# Schematic_v2_0.net
KiCad netlist of a schematic drawn in EAGLE
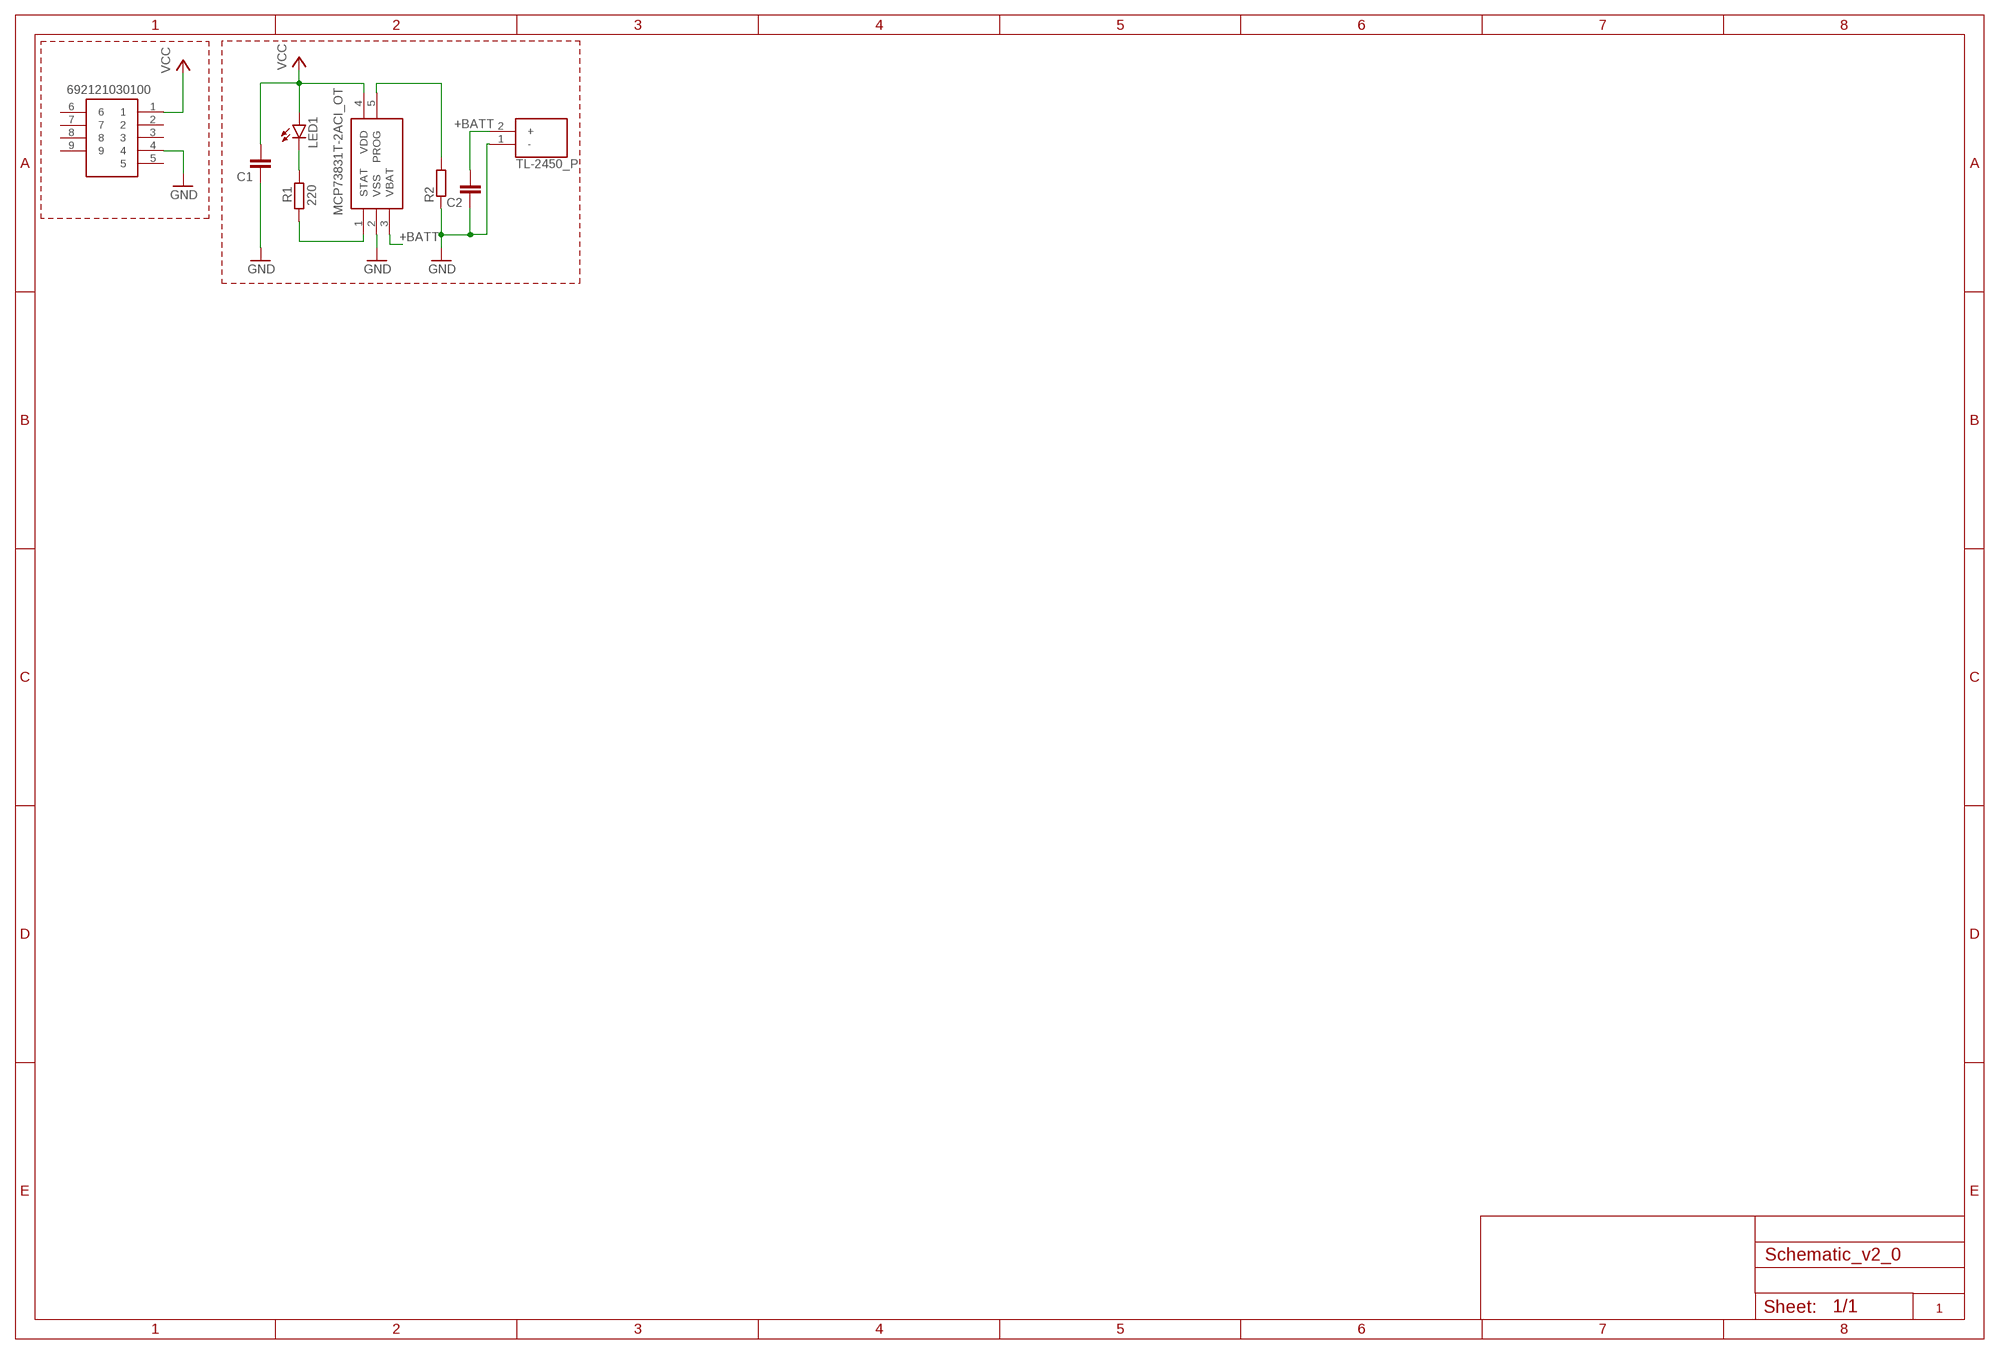
[diagram p0: schematic, sheet 1]

(export (version "E")
  (design (tool "Eeschema 10.0.6"))
  (components
    (comp (ref "BT1")
      (value "TL-2450_P")
      (footprint "eagle-import:TL2450P")
      (fields (field (name "ARROW_PART_NUMBER") "TL-2450/P"))
      (libsource (lib "eagle-import") (part "TL-2450_P"))
    )
    (comp (ref "C1")
      (value "C-EUC0805")
      (footprint "eagle-import:C0805")
      (libsource (lib "eagle-import") (part "C-EUC0805"))
    )
    (comp (ref "C2")
      (value "C-EUC0805")
      (footprint "eagle-import:C0805")
      (libsource (lib "eagle-import") (part "C-EUC0805"))
    )
    (comp (ref "IC1")
      (value "MCP73831T-2ACI_OT")
      (footprint "eagle-import:SOT95P270X145-5N")
      (fields
        (field (name "ARROW_PART_NUMBER") "MCP73831T-2ACI/OT")
        (field (name "MOUSER_PART_NUMBER") "579-MCP73831T-2ACIOT")
      )
      (libsource (lib "eagle-import") (part "MCP73831T-2ACI_OT"))
    )
    (comp (ref "J1")
      (value "692121030100")
      (footprint "eagle-import:692121030100")
      (fields (field (name "MOUSER_PART_NUMBER") "710-692121030100"))
      (libsource (lib "eagle-import") (part "692121030100"))
    )
    (comp (ref "LED1")
      (value "LEDCHIP-LED0805")
      (footprint "eagle-import:CHIP-LED0805")
      (libsource (lib "eagle-import") (part "LEDCHIP-LED0805"))
    )
    (comp (ref "R1")
      (value "220")
      (footprint "eagle-import:R0805")
      (libsource (lib "eagle-import") (part "R-EU_R0805"))
    )
    (comp (ref "R2")
      (value "R-EU_R0805")
      (footprint "eagle-import:R0805")
      (libsource (lib "eagle-import") (part "R-EU_R0805"))
    )
  )
  (nets
    (net (code "1") (name "/+BATT") (class "Default")
      (node (ref "BT1") (pin "2") (pinfunction "+_2") (pintype "bidirectional"))
      (node (ref "C2") (pin "2") (pinfunction "2_2") (pintype "passive"))
      (node (ref "IC1") (pin "3") (pinfunction "VBAT_3") (pintype "bidirectional"))
    )
    (net (code "2") (name "GND") (class "Default")
      (node (ref "BT1") (pin "1") (pinfunction "-_1") (pintype "bidirectional"))
      (node (ref "C1") (pin "1") (pinfunction "1_1") (pintype "passive"))
      (node (ref "C2") (pin "1") (pinfunction "1_1") (pintype "passive"))
      (node (ref "IC1") (pin "2") (pinfunction "VSS_2") (pintype "bidirectional"))
      (node (ref "J1") (pin "4") (pinfunction "4_4") (pintype "bidirectional"))
      (node (ref "R2") (pin "1") (pinfunction "1_1") (pintype "passive"))
    )
    (net (code "3") (name "Net-(IC1-PROG)") (class "Default")
      (node (ref "IC1") (pin "5") (pinfunction "PROG_5") (pintype "bidirectional"))
      (node (ref "R2") (pin "2") (pinfunction "2_2") (pintype "passive"))
    )
    (net (code "4") (name "Net-(IC1-STAT)") (class "Default")
      (node (ref "IC1") (pin "1") (pinfunction "STAT_1") (pintype "bidirectional"))
      (node (ref "R1") (pin "1") (pinfunction "1_1") (pintype "passive"))
    )
    (net (code "5") (name "Net-(LED1-PadC)") (class "Default")
      (node (ref "LED1") (pin "C") (pinfunction "C_C") (pintype "passive"))
      (node (ref "R1") (pin "2") (pinfunction "2_2") (pintype "passive"))
    )
    (net (code "6") (name "VCC") (class "Default")
      (node (ref "C1") (pin "2") (pinfunction "2_2") (pintype "passive"))
      (node (ref "IC1") (pin "4") (pinfunction "VDD_4") (pintype "bidirectional"))
      (node (ref "J1") (pin "1") (pinfunction "1_1") (pintype "bidirectional"))
      (node (ref "LED1") (pin "A") (pinfunction "A_A") (pintype "passive"))
    )
    (net (code "7") (name "unconnected-(J1-Pad2)") (class "Default")
      (node (ref "J1") (pin "2") (pinfunction "2_2") (pintype "bidirectional"))
    )
    (net (code "8") (name "unconnected-(J1-Pad3)") (class "Default")
      (node (ref "J1") (pin "3") (pinfunction "3_3") (pintype "bidirectional"))
    )
    (net (code "9") (name "unconnected-(J1-Pad5)") (class "Default")
      (node (ref "J1") (pin "5") (pinfunction "5_5") (pintype "bidirectional"))
    )
    (net (code "10") (name "unconnected-(J1-Pad6)") (class "Default")
      (node (ref "J1") (pin "6") (pinfunction "6_6") (pintype "bidirectional"))
    )
    (net (code "11") (name "unconnected-(J1-Pad7)") (class "Default")
      (node (ref "J1") (pin "7") (pinfunction "7_7") (pintype "bidirectional"))
    )
    (net (code "12") (name "unconnected-(J1-Pad8)") (class "Default")
      (node (ref "J1") (pin "8") (pinfunction "8_8") (pintype "bidirectional"))
    )
    (net (code "13") (name "unconnected-(J1-Pad9)") (class "Default")
      (node (ref "J1") (pin "9") (pinfunction "9_9") (pintype "bidirectional"))
    )
  )
)
